# SigCapture3.net
KiCad netlist of a schematic drawn in Altium Designer
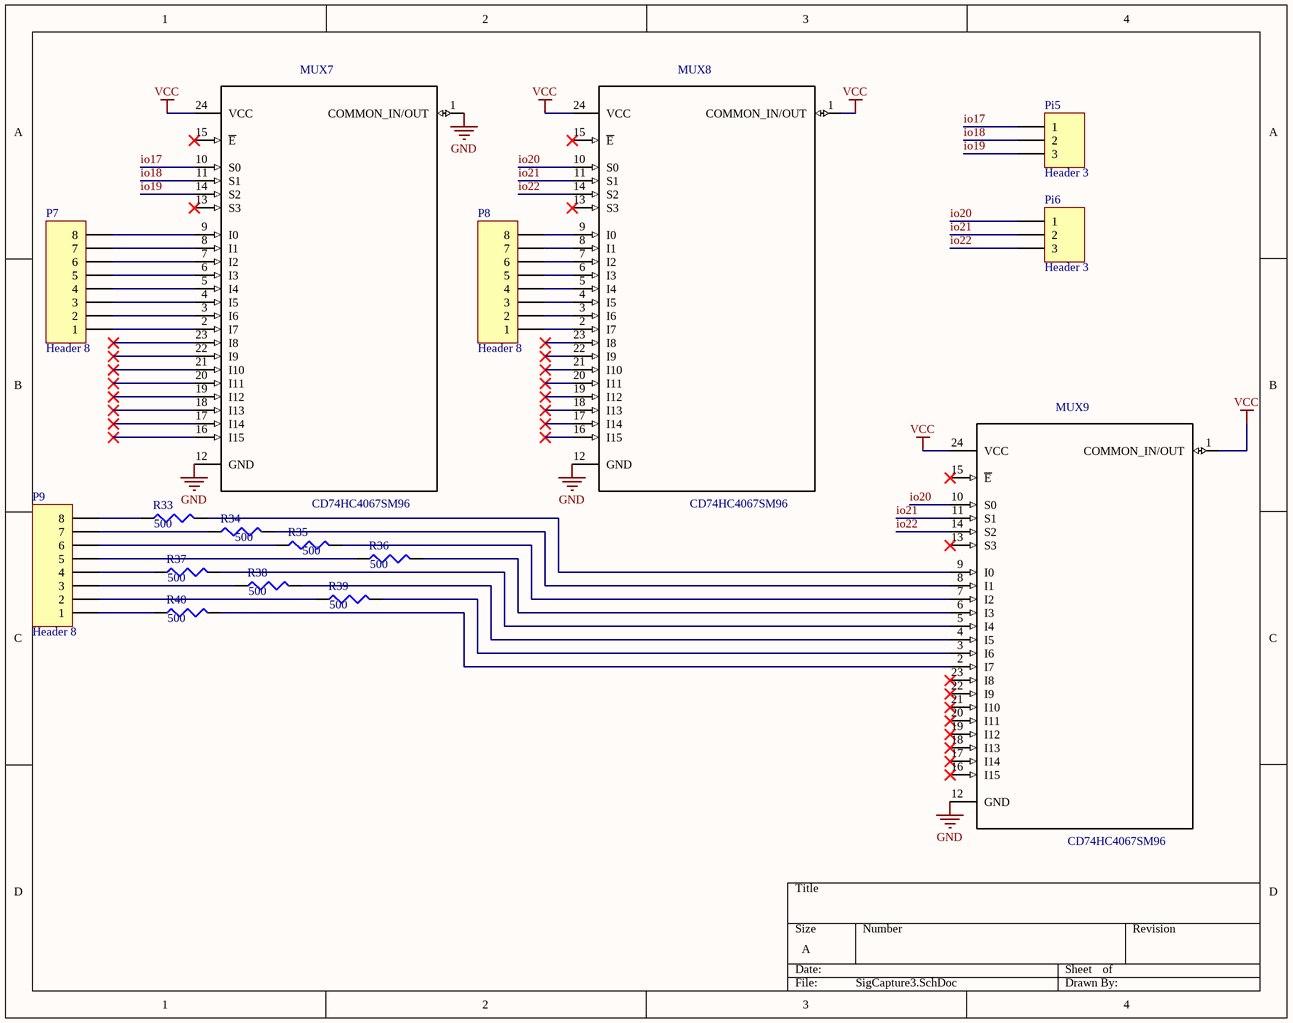
[diagram p0: SigCapture3.SchDoc]

(export (version "E")
  (design (tool "Eeschema 10.0.6"))
  (components
    (comp (ref "MUX7")
      (value "CD74HC4067SM96")
      (footprint "SOP65P780X200-24N")
      (description "High Speed CMOS 16-Channel Analog Multiplexer/Demultiplexer 24-SSOP -55 to 125")
      (fields (field (name "MF") "Texas Instruments"))
      (libsource (lib "CD74HC4067SM96") (part "CD74HC4067SM96"))
    )
    (comp (ref "MUX8")
      (value "CD74HC4067SM96")
      (footprint "SOP65P780X200-24N")
      (description "High Speed CMOS 16-Channel Analog Multiplexer/Demultiplexer 24-SSOP -55 to 125")
      (fields (field (name "MF") "Texas Instruments"))
      (libsource (lib "CD74HC4067SM96") (part "CD74HC4067SM96"))
    )
    (comp (ref "MUX9")
      (value "CD74HC4067SM96")
      (footprint "SOP65P780X200-24N")
      (description "High Speed CMOS 16-Channel Analog Multiplexer/Demultiplexer 24-SSOP -55 to 125")
      (fields (field (name "MF") "Texas Instruments"))
      (libsource (lib "CD74HC4067SM96") (part "CD74HC4067SM96"))
    )
    (comp (ref "P7")
      (value "Header 8")
      (footprint "HDR1X8")
      (description "Header, 8-Pin")
      (fields (field (name "PUBLISHER") "Altium Limited"))
      (libsource (lib "Miscellaneous Connectors") (part "Header 8"))
    )
    (comp (ref "P8")
      (value "Header 8")
      (footprint "HDR1X8")
      (description "Header, 8-Pin")
      (fields (field (name "PUBLISHER") "Altium Limited"))
      (libsource (lib "Miscellaneous Connectors") (part "Header 8"))
    )
    (comp (ref "P9")
      (value "Header 8")
      (footprint "HDR1X8")
      (description "Header, 8-Pin")
      (fields (field (name "PUBLISHER") "Altium Limited"))
      (libsource (lib "Miscellaneous Connectors") (part "Header 8"))
    )
    (comp (ref "Pi5")
      (value "Header 3")
      (footprint "HDR1X3")
      (description "Header, 3-Pin")
      (fields (field (name "PUBLISHER") "Altium Limited"))
      (libsource (lib "Miscellaneous Connectors") (part "Header 3"))
    )
    (comp (ref "Pi6")
      (value "Header 3")
      (footprint "HDR1X3")
      (description "Header, 3-Pin")
      (fields (field (name "PUBLISHER") "Altium Limited"))
      (libsource (lib "Miscellaneous Connectors") (part "Header 3"))
    )
    (comp (ref "R33")
      (value "500")
      (footprint "J1-0603")
      (description "Resistor")
      (fields (field (name "Comment") "Res3") (field (name "PUBLISHER") "Altium Limited"))
      (libsource (lib "Miscellaneous Devices") (part "Res3"))
    )
    (comp (ref "R34")
      (value "500")
      (footprint "J1-0603")
      (description "Resistor")
      (fields (field (name "Comment") "Res3") (field (name "PUBLISHER") "Altium Limited"))
      (libsource (lib "Miscellaneous Devices") (part "Res3"))
    )
    (comp (ref "R35")
      (value "500")
      (footprint "J1-0603")
      (description "Resistor")
      (fields (field (name "Comment") "Res3") (field (name "PUBLISHER") "Altium Limited"))
      (libsource (lib "Miscellaneous Devices") (part "Res3"))
    )
    (comp (ref "R36")
      (value "500")
      (footprint "J1-0603")
      (description "Resistor")
      (fields (field (name "Comment") "Res3") (field (name "PUBLISHER") "Altium Limited"))
      (libsource (lib "Miscellaneous Devices") (part "Res3"))
    )
    (comp (ref "R37")
      (value "500")
      (footprint "J1-0603")
      (description "Resistor")
      (fields (field (name "Comment") "Res3") (field (name "PUBLISHER") "Altium Limited"))
      (libsource (lib "Miscellaneous Devices") (part "Res3"))
    )
    (comp (ref "R38")
      (value "500")
      (footprint "J1-0603")
      (description "Resistor")
      (fields (field (name "Comment") "Res3") (field (name "PUBLISHER") "Altium Limited"))
      (libsource (lib "Miscellaneous Devices") (part "Res3"))
    )
    (comp (ref "R39")
      (value "500")
      (footprint "J1-0603")
      (description "Resistor")
      (fields (field (name "Comment") "Res3") (field (name "PUBLISHER") "Altium Limited"))
      (libsource (lib "Miscellaneous Devices") (part "Res3"))
    )
    (comp (ref "R40")
      (value "500")
      (footprint "J1-0603")
      (description "Resistor")
      (fields (field (name "Comment") "Res3") (field (name "PUBLISHER") "Altium Limited"))
      (libsource (lib "Miscellaneous Devices") (part "Res3"))
    )
  )
  (nets
    (net (code "1") (name "/io17") (class "Default")
      (node (ref "MUX7") (pin "10") (pinfunction "S0_10") (pintype "input"))
      (node (ref "Pi5") (pin "1") (pinfunction "1_1") (pintype "passive"))
    )
    (net (code "2") (name "/io18") (class "Default")
      (node (ref "MUX7") (pin "11") (pinfunction "S1_11") (pintype "input"))
      (node (ref "Pi5") (pin "2") (pinfunction "2_2") (pintype "passive"))
    )
    (net (code "3") (name "/io19") (class "Default")
      (node (ref "MUX7") (pin "14") (pinfunction "S2_14") (pintype "input"))
      (node (ref "Pi5") (pin "3") (pinfunction "3_3") (pintype "passive"))
    )
    (net (code "4") (name "/io20") (class "Default")
      (node (ref "MUX8") (pin "10") (pinfunction "S0_10") (pintype "input"))
      (node (ref "MUX9") (pin "10") (pinfunction "S0_10") (pintype "input"))
      (node (ref "Pi6") (pin "1") (pinfunction "1_1") (pintype "passive"))
    )
    (net (code "5") (name "/io21") (class "Default")
      (node (ref "MUX8") (pin "11") (pinfunction "S1_11") (pintype "input"))
      (node (ref "MUX9") (pin "11") (pinfunction "S1_11") (pintype "input"))
      (node (ref "Pi6") (pin "2") (pinfunction "2_2") (pintype "passive"))
    )
    (net (code "6") (name "/io22") (class "Default")
      (node (ref "MUX8") (pin "14") (pinfunction "S2_14") (pintype "input"))
      (node (ref "MUX9") (pin "14") (pinfunction "S2_14") (pintype "input"))
      (node (ref "Pi6") (pin "3") (pinfunction "3_3") (pintype "passive"))
    )
    (net (code "7") (name "GND") (class "Default")
      (node (ref "MUX7") (pin "1") (pinfunction "COMMON_IN/OUT_1") (pintype "bidirectional"))
      (node (ref "MUX7") (pin "12") (pinfunction "GND_12") (pintype "passive"))
      (node (ref "MUX8") (pin "12") (pinfunction "GND_12") (pintype "passive"))
      (node (ref "MUX9") (pin "12") (pinfunction "GND_12") (pintype "passive"))
    )
    (net (code "8") (name "Net-(MUX7-I0)") (class "Default")
      (node (ref "MUX7") (pin "9") (pinfunction "I0_9") (pintype "input"))
      (node (ref "P7") (pin "8") (pinfunction "8_8") (pintype "passive"))
    )
    (net (code "9") (name "Net-(MUX7-I1)") (class "Default")
      (node (ref "MUX7") (pin "8") (pinfunction "I1_8") (pintype "input"))
      (node (ref "P7") (pin "7") (pinfunction "7_7") (pintype "passive"))
    )
    (net (code "10") (name "Net-(MUX7-I2)") (class "Default")
      (node (ref "MUX7") (pin "7") (pinfunction "I2_7") (pintype "input"))
      (node (ref "P7") (pin "6") (pinfunction "6_6") (pintype "passive"))
    )
    (net (code "11") (name "Net-(MUX7-I3)") (class "Default")
      (node (ref "MUX7") (pin "6") (pinfunction "I3_6") (pintype "input"))
      (node (ref "P7") (pin "5") (pinfunction "5_5") (pintype "passive"))
    )
    (net (code "12") (name "Net-(MUX7-I4)") (class "Default")
      (node (ref "MUX7") (pin "5") (pinfunction "I4_5") (pintype "input"))
      (node (ref "P7") (pin "4") (pinfunction "4_4") (pintype "passive"))
    )
    (net (code "13") (name "Net-(MUX7-I5)") (class "Default")
      (node (ref "MUX7") (pin "4") (pinfunction "I5_4") (pintype "input"))
      (node (ref "P7") (pin "3") (pinfunction "3_3") (pintype "passive"))
    )
    (net (code "14") (name "Net-(MUX7-I6)") (class "Default")
      (node (ref "MUX7") (pin "3") (pinfunction "I6_3") (pintype "input"))
      (node (ref "P7") (pin "2") (pinfunction "2_2") (pintype "passive"))
    )
    (net (code "15") (name "Net-(MUX7-I7)") (class "Default")
      (node (ref "MUX7") (pin "2") (pinfunction "I7_2") (pintype "input"))
      (node (ref "P7") (pin "1") (pinfunction "1_1") (pintype "passive"))
    )
    (net (code "16") (name "Net-(MUX8-I0)") (class "Default")
      (node (ref "MUX8") (pin "9") (pinfunction "I0_9") (pintype "input"))
      (node (ref "P8") (pin "8") (pinfunction "8_8") (pintype "passive"))
    )
    (net (code "17") (name "Net-(MUX8-I1)") (class "Default")
      (node (ref "MUX8") (pin "8") (pinfunction "I1_8") (pintype "input"))
      (node (ref "P8") (pin "7") (pinfunction "7_7") (pintype "passive"))
    )
    (net (code "18") (name "Net-(MUX8-I2)") (class "Default")
      (node (ref "MUX8") (pin "7") (pinfunction "I2_7") (pintype "input"))
      (node (ref "P8") (pin "6") (pinfunction "6_6") (pintype "passive"))
    )
    (net (code "19") (name "Net-(MUX8-I3)") (class "Default")
      (node (ref "MUX8") (pin "6") (pinfunction "I3_6") (pintype "input"))
      (node (ref "P8") (pin "5") (pinfunction "5_5") (pintype "passive"))
    )
    (net (code "20") (name "Net-(MUX8-I4)") (class "Default")
      (node (ref "MUX8") (pin "5") (pinfunction "I4_5") (pintype "input"))
      (node (ref "P8") (pin "4") (pinfunction "4_4") (pintype "passive"))
    )
    (net (code "21") (name "Net-(MUX8-I5)") (class "Default")
      (node (ref "MUX8") (pin "4") (pinfunction "I5_4") (pintype "input"))
      (node (ref "P8") (pin "3") (pinfunction "3_3") (pintype "passive"))
    )
    (net (code "22") (name "Net-(MUX8-I6)") (class "Default")
      (node (ref "MUX8") (pin "3") (pinfunction "I6_3") (pintype "input"))
      (node (ref "P8") (pin "2") (pinfunction "2_2") (pintype "passive"))
    )
    (net (code "23") (name "Net-(MUX8-I7)") (class "Default")
      (node (ref "MUX8") (pin "2") (pinfunction "I7_2") (pintype "input"))
      (node (ref "P8") (pin "1") (pinfunction "1_1") (pintype "passive"))
    )
    (net (code "24") (name "Net-(MUX9-I0)") (class "Default")
      (node (ref "MUX9") (pin "9") (pinfunction "I0_9") (pintype "input"))
      (node (ref "R33") (pin "2") (pinfunction "2_2") (pintype "passive"))
    )
    (net (code "25") (name "Net-(MUX9-I1)") (class "Default")
      (node (ref "MUX9") (pin "8") (pinfunction "I1_8") (pintype "input"))
      (node (ref "R34") (pin "2") (pinfunction "2_2") (pintype "passive"))
    )
    (net (code "26") (name "Net-(MUX9-I2)") (class "Default")
      (node (ref "MUX9") (pin "7") (pinfunction "I2_7") (pintype "input"))
      (node (ref "R35") (pin "2") (pinfunction "2_2") (pintype "passive"))
    )
    (net (code "27") (name "Net-(MUX9-I3)") (class "Default")
      (node (ref "MUX9") (pin "6") (pinfunction "I3_6") (pintype "input"))
      (node (ref "R36") (pin "2") (pinfunction "2_2") (pintype "passive"))
    )
    (net (code "28") (name "Net-(MUX9-I4)") (class "Default")
      (node (ref "MUX9") (pin "5") (pinfunction "I4_5") (pintype "input"))
      (node (ref "R37") (pin "2") (pinfunction "2_2") (pintype "passive"))
    )
    (net (code "29") (name "Net-(MUX9-I5)") (class "Default")
      (node (ref "MUX9") (pin "4") (pinfunction "I5_4") (pintype "input"))
      (node (ref "R38") (pin "2") (pinfunction "2_2") (pintype "passive"))
    )
    (net (code "30") (name "Net-(MUX9-I6)") (class "Default")
      (node (ref "MUX9") (pin "3") (pinfunction "I6_3") (pintype "input"))
      (node (ref "R39") (pin "2") (pinfunction "2_2") (pintype "passive"))
    )
    (net (code "31") (name "Net-(MUX9-I7)") (class "Default")
      (node (ref "MUX9") (pin "2") (pinfunction "I7_2") (pintype "input"))
      (node (ref "R40") (pin "2") (pinfunction "2_2") (pintype "passive"))
    )
    (net (code "32") (name "Net-(P9-Pad1)") (class "Default")
      (node (ref "P9") (pin "1") (pinfunction "1_1") (pintype "passive"))
      (node (ref "R40") (pin "1") (pinfunction "1_1") (pintype "passive"))
    )
    (net (code "33") (name "Net-(P9-Pad2)") (class "Default")
      (node (ref "P9") (pin "2") (pinfunction "2_2") (pintype "passive"))
      (node (ref "R39") (pin "1") (pinfunction "1_1") (pintype "passive"))
    )
    (net (code "34") (name "Net-(P9-Pad3)") (class "Default")
      (node (ref "P9") (pin "3") (pinfunction "3_3") (pintype "passive"))
      (node (ref "R38") (pin "1") (pinfunction "1_1") (pintype "passive"))
    )
    (net (code "35") (name "Net-(P9-Pad4)") (class "Default")
      (node (ref "P9") (pin "4") (pinfunction "4_4") (pintype "passive"))
      (node (ref "R37") (pin "1") (pinfunction "1_1") (pintype "passive"))
    )
    (net (code "36") (name "Net-(P9-Pad5)") (class "Default")
      (node (ref "P9") (pin "5") (pinfunction "5_5") (pintype "passive"))
      (node (ref "R36") (pin "1") (pinfunction "1_1") (pintype "passive"))
    )
    (net (code "37") (name "Net-(P9-Pad6)") (class "Default")
      (node (ref "P9") (pin "6") (pinfunction "6_6") (pintype "passive"))
      (node (ref "R35") (pin "1") (pinfunction "1_1") (pintype "passive"))
    )
    (net (code "38") (name "Net-(P9-Pad7)") (class "Default")
      (node (ref "P9") (pin "7") (pinfunction "7_7") (pintype "passive"))
      (node (ref "R34") (pin "1") (pinfunction "1_1") (pintype "passive"))
    )
    (net (code "39") (name "Net-(P9-Pad8)") (class "Default")
      (node (ref "P9") (pin "8") (pinfunction "8_8") (pintype "passive"))
      (node (ref "R33") (pin "1") (pinfunction "1_1") (pintype "passive"))
    )
    (net (code "40") (name "VCC") (class "Default")
      (node (ref "MUX7") (pin "24") (pinfunction "VCC_24") (pintype "power_in"))
      (node (ref "MUX8") (pin "1") (pinfunction "COMMON_IN/OUT_1") (pintype "bidirectional"))
      (node (ref "MUX8") (pin "24") (pinfunction "VCC_24") (pintype "power_in"))
      (node (ref "MUX9") (pin "1") (pinfunction "COMMON_IN/OUT_1") (pintype "bidirectional"))
      (node (ref "MUX9") (pin "24") (pinfunction "VCC_24") (pintype "power_in"))
    )
    (net (code "41") (name "unconnected-(MUX7-I8-Pad23)") (class "Default")
      (node (ref "MUX7") (pin "23") (pinfunction "I8_23") (pintype "input+no_connect"))
    )
    (net (code "42") (name "unconnected-(MUX7-I9-Pad22)") (class "Default")
      (node (ref "MUX7") (pin "22") (pinfunction "I9_22") (pintype "input+no_connect"))
    )
    (net (code "43") (name "unconnected-(MUX7-I10-Pad21)") (class "Default")
      (node (ref "MUX7") (pin "21") (pinfunction "I10_21") (pintype "input+no_connect"))
    )
    (net (code "44") (name "unconnected-(MUX7-I11-Pad20)") (class "Default")
      (node (ref "MUX7") (pin "20") (pinfunction "I11_20") (pintype "input+no_connect"))
    )
    (net (code "45") (name "unconnected-(MUX7-I12-Pad19)") (class "Default")
      (node (ref "MUX7") (pin "19") (pinfunction "I12_19") (pintype "input+no_connect"))
    )
    (net (code "46") (name "unconnected-(MUX7-I13-Pad18)") (class "Default")
      (node (ref "MUX7") (pin "18") (pinfunction "I13_18") (pintype "input+no_connect"))
    )
    (net (code "47") (name "unconnected-(MUX7-I14-Pad17)") (class "Default")
      (node (ref "MUX7") (pin "17") (pinfunction "I14_17") (pintype "input+no_connect"))
    )
    (net (code "48") (name "unconnected-(MUX7-I15-Pad16)") (class "Default")
      (node (ref "MUX7") (pin "16") (pinfunction "I15_16") (pintype "input+no_connect"))
    )
    (net (code "49") (name "unconnected-(MUX7-S3-Pad13)") (class "Default")
      (node (ref "MUX7") (pin "13") (pinfunction "S3_13") (pintype "input+no_connect"))
    )
    (net (code "50") (name "unconnected-(MUX7-~{E}-Pad15)") (class "Default")
      (node (ref "MUX7") (pin "15") (pinfunction "~{E}_15") (pintype "input+no_connect"))
    )
    (net (code "51") (name "unconnected-(MUX8-I8-Pad23)") (class "Default")
      (node (ref "MUX8") (pin "23") (pinfunction "I8_23") (pintype "input+no_connect"))
    )
    (net (code "52") (name "unconnected-(MUX8-I9-Pad22)") (class "Default")
      (node (ref "MUX8") (pin "22") (pinfunction "I9_22") (pintype "input+no_connect"))
    )
    (net (code "53") (name "unconnected-(MUX8-I10-Pad21)") (class "Default")
      (node (ref "MUX8") (pin "21") (pinfunction "I10_21") (pintype "input+no_connect"))
    )
    (net (code "54") (name "unconnected-(MUX8-I11-Pad20)") (class "Default")
      (node (ref "MUX8") (pin "20") (pinfunction "I11_20") (pintype "input+no_connect"))
    )
    (net (code "55") (name "unconnected-(MUX8-I12-Pad19)") (class "Default")
      (node (ref "MUX8") (pin "19") (pinfunction "I12_19") (pintype "input+no_connect"))
    )
    (net (code "56") (name "unconnected-(MUX8-I13-Pad18)") (class "Default")
      (node (ref "MUX8") (pin "18") (pinfunction "I13_18") (pintype "input+no_connect"))
    )
    (net (code "57") (name "unconnected-(MUX8-I14-Pad17)") (class "Default")
      (node (ref "MUX8") (pin "17") (pinfunction "I14_17") (pintype "input+no_connect"))
    )
    (net (code "58") (name "unconnected-(MUX8-I15-Pad16)") (class "Default")
      (node (ref "MUX8") (pin "16") (pinfunction "I15_16") (pintype "input+no_connect"))
    )
    (net (code "59") (name "unconnected-(MUX8-S3-Pad13)") (class "Default")
      (node (ref "MUX8") (pin "13") (pinfunction "S3_13") (pintype "input+no_connect"))
    )
    (net (code "60") (name "unconnected-(MUX8-~{E}-Pad15)") (class "Default")
      (node (ref "MUX8") (pin "15") (pinfunction "~{E}_15") (pintype "input+no_connect"))
    )
    (net (code "61") (name "unconnected-(MUX9-I8-Pad23)") (class "Default")
      (node (ref "MUX9") (pin "23") (pinfunction "I8_23") (pintype "input+no_connect"))
    )
    (net (code "62") (name "unconnected-(MUX9-I9-Pad22)") (class "Default")
      (node (ref "MUX9") (pin "22") (pinfunction "I9_22") (pintype "input+no_connect"))
    )
    (net (code "63") (name "unconnected-(MUX9-I10-Pad21)") (class "Default")
      (node (ref "MUX9") (pin "21") (pinfunction "I10_21") (pintype "input+no_connect"))
    )
    (net (code "64") (name "unconnected-(MUX9-I11-Pad20)") (class "Default")
      (node (ref "MUX9") (pin "20") (pinfunction "I11_20") (pintype "input+no_connect"))
    )
    (net (code "65") (name "unconnected-(MUX9-I12-Pad19)") (class "Default")
      (node (ref "MUX9") (pin "19") (pinfunction "I12_19") (pintype "input+no_connect"))
    )
    (net (code "66") (name "unconnected-(MUX9-I13-Pad18)") (class "Default")
      (node (ref "MUX9") (pin "18") (pinfunction "I13_18") (pintype "input+no_connect"))
    )
    (net (code "67") (name "unconnected-(MUX9-I14-Pad17)") (class "Default")
      (node (ref "MUX9") (pin "17") (pinfunction "I14_17") (pintype "input+no_connect"))
    )
    (net (code "68") (name "unconnected-(MUX9-I15-Pad16)") (class "Default")
      (node (ref "MUX9") (pin "16") (pinfunction "I15_16") (pintype "input+no_connect"))
    )
    (net (code "69") (name "unconnected-(MUX9-S3-Pad13)") (class "Default")
      (node (ref "MUX9") (pin "13") (pinfunction "S3_13") (pintype "input+no_connect"))
    )
    (net (code "70") (name "unconnected-(MUX9-~{E}-Pad15)") (class "Default")
      (node (ref "MUX9") (pin "15") (pinfunction "~{E}_15") (pintype "input+no_connect"))
    )
  )
)
